# pam2803-boost-driver-13mm-mk-1_1.net
KiCad netlist of a schematic drawn in EAGLE
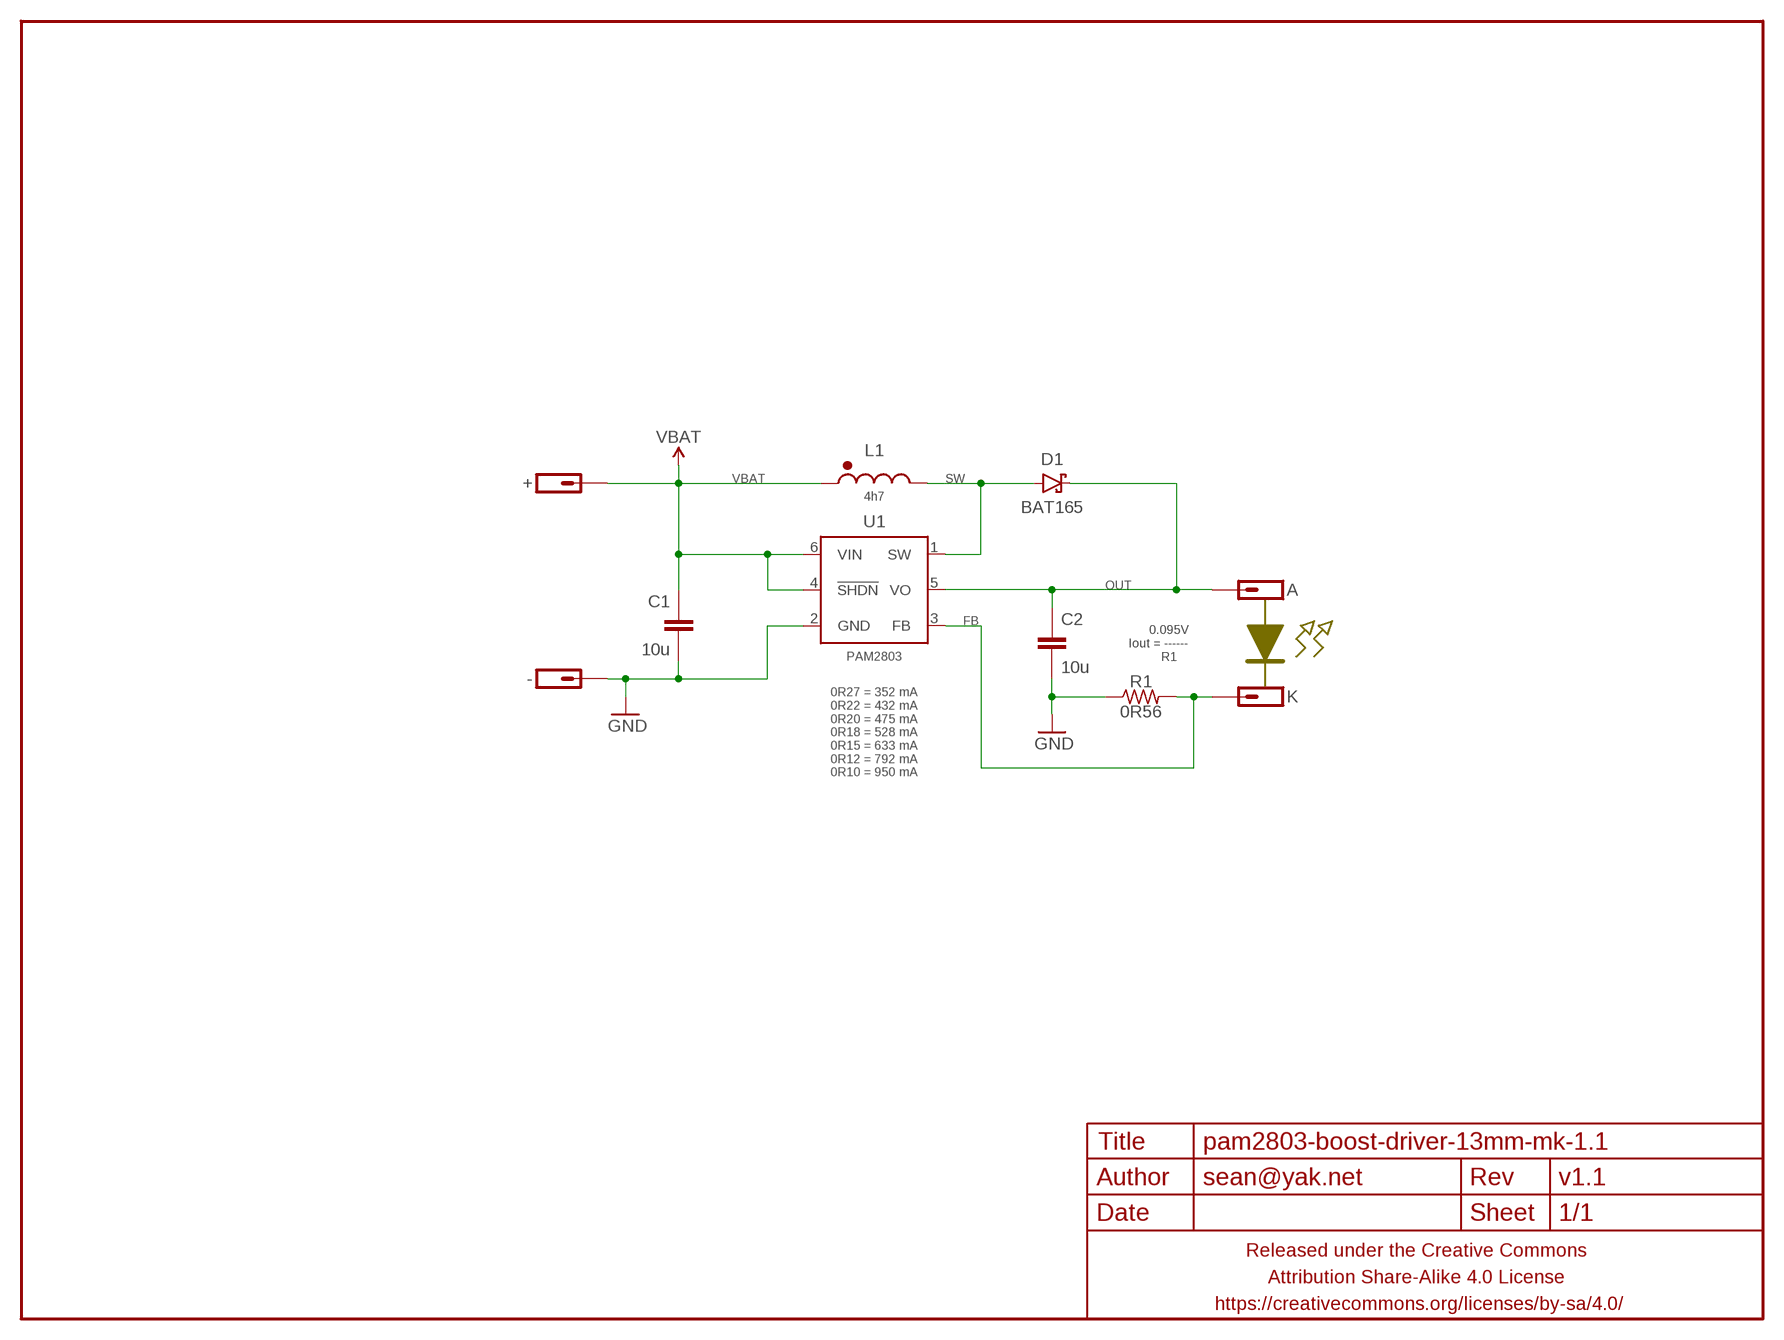
[diagram p0: schematic, sheet 1]

(export (version "E")
  (design (tool "Eeschema 10.0.6"))
  (components
    (comp (ref "+")
      (value "M01NOT-A-VIA-NOPE")
      (footprint "eagle-import:1X01_NOSILK_NOSTOP")
      (libsource (lib "eagle-import") (part "M01NOT-A-VIA-NOPE"))
    )
    (comp (ref "-")
      (value "M01NOT-A-VIA-NOPE")
      (footprint "eagle-import:1X01_NOSILK_NOSTOP")
      (libsource (lib "eagle-import") (part "M01NOT-A-VIA-NOPE"))
    )
    (comp (ref "A")
      (value "M01SMD-1.5MM-DIA-NS")
      (footprint "eagle-import:1X01-SMD-1.5MM-DIA-NS")
      (libsource (lib "eagle-import") (part "M01SMD-1.5MM-DIA-NS"))
    )
    (comp (ref "C1")
      (value "10u")
      (footprint "eagle-import:C0603-TIGHTER")
      (libsource (lib "eagle-import") (part "CAPACITOR-CERAMICC0603-TIGHTER"))
    )
    (comp (ref "C2")
      (value "10u")
      (footprint "eagle-import:C0603-TIGHTER")
      (libsource (lib "eagle-import") (part "CAPACITOR-CERAMICC0603-TIGHTER"))
    )
    (comp (ref "D1")
      (value "BAT165")
      (footprint "eagle-import:SOD323-SCHOTTKY")
      (libsource (lib "eagle-import") (part "DIODE-SCHOTTKYSOD323"))
    )
    (comp (ref "FRAME1")
      (value "FRAME-LETTERNO_PACKAGE")
      (footprint "eagle-import:DUMMY")
      (fields (field (name "DESIGNER") "sean@yak.net") (field (name "VERSION") "v1.1"))
      (libsource (lib "eagle-import") (part "FRAME-LETTERNO_PACKAGE"))
    )
    (comp (ref "K")
      (value "M01SMD-1.5MM-DIA-NS")
      (footprint "eagle-import:1X01-SMD-1.5MM-DIA-NS")
      (libsource (lib "eagle-import") (part "M01SMD-1.5MM-DIA-NS"))
    )
    (comp (ref "L1")
      (value "4h7")
      (footprint "eagle-import:EPL2014")
      (libsource (lib "eagle-import") (part "INDUCTOREPL2014"))
    )
    (comp (ref "R1")
      (value "0R56")
      (footprint "eagle-import:R0603-TIGHTER")
      (libsource (lib "eagle-import") (part "RESISTORR0603-TIGHTER"))
    )
    (comp (ref "U1")
      (value "PAM2803")
      (footprint "eagle-import:SOT23-6")
      (libsource (lib "eagle-import") (part "PAM2803SOT23-6"))
    )
  )
  (nets
    (net (code "1") (name "/FB") (class "Default")
      (node (ref "K") (pin "P$1") (pinfunction "1_P$1") (pintype "passive"))
      (node (ref "R1") (pin "2") (pinfunction "2_2") (pintype "passive"))
      (node (ref "U1") (pin "3") (pinfunction "FB_3") (pintype "bidirectional"))
    )
    (net (code "2") (name "/OUT") (class "Default")
      (node (ref "A") (pin "P$1") (pinfunction "1_P$1") (pintype "passive"))
      (node (ref "C2") (pin "1") (pinfunction "1_1") (pintype "passive"))
      (node (ref "D1") (pin "C") (pinfunction "C_C") (pintype "passive"))
      (node (ref "U1") (pin "5") (pinfunction "VO_5") (pintype "bidirectional"))
    )
    (net (code "3") (name "/SW") (class "Default")
      (node (ref "D1") (pin "A") (pinfunction "A_A") (pintype "passive"))
      (node (ref "L1") (pin "P$2") (pinfunction "2_P$2") (pintype "passive"))
      (node (ref "U1") (pin "1") (pinfunction "SW_1") (pintype "bidirectional"))
    )
    (net (code "4") (name "GND") (class "Default")
      (node (ref "-") (pin "P$1") (pinfunction "1_P$1") (pintype "passive"))
      (node (ref "C1") (pin "2") (pinfunction "2_2") (pintype "passive"))
      (node (ref "C2") (pin "2") (pinfunction "2_2") (pintype "passive"))
      (node (ref "R1") (pin "1") (pinfunction "1_1") (pintype "passive"))
      (node (ref "U1") (pin "2") (pinfunction "GND_2") (pintype "bidirectional"))
    )
    (net (code "5") (name "VBAT") (class "Default")
      (node (ref "+") (pin "P$1") (pinfunction "1_P$1") (pintype "passive"))
      (node (ref "C1") (pin "1") (pinfunction "1_1") (pintype "passive"))
      (node (ref "L1") (pin "P$1") (pinfunction "1_P$1") (pintype "passive"))
      (node (ref "U1") (pin "4") (pinfunction "~{SHDN}_4") (pintype "bidirectional"))
      (node (ref "U1") (pin "6") (pinfunction "VIN_6") (pintype "bidirectional"))
    )
  )
)
